# 1_P1.net
KiCad netlist of a schematic drawn in Altium Designer
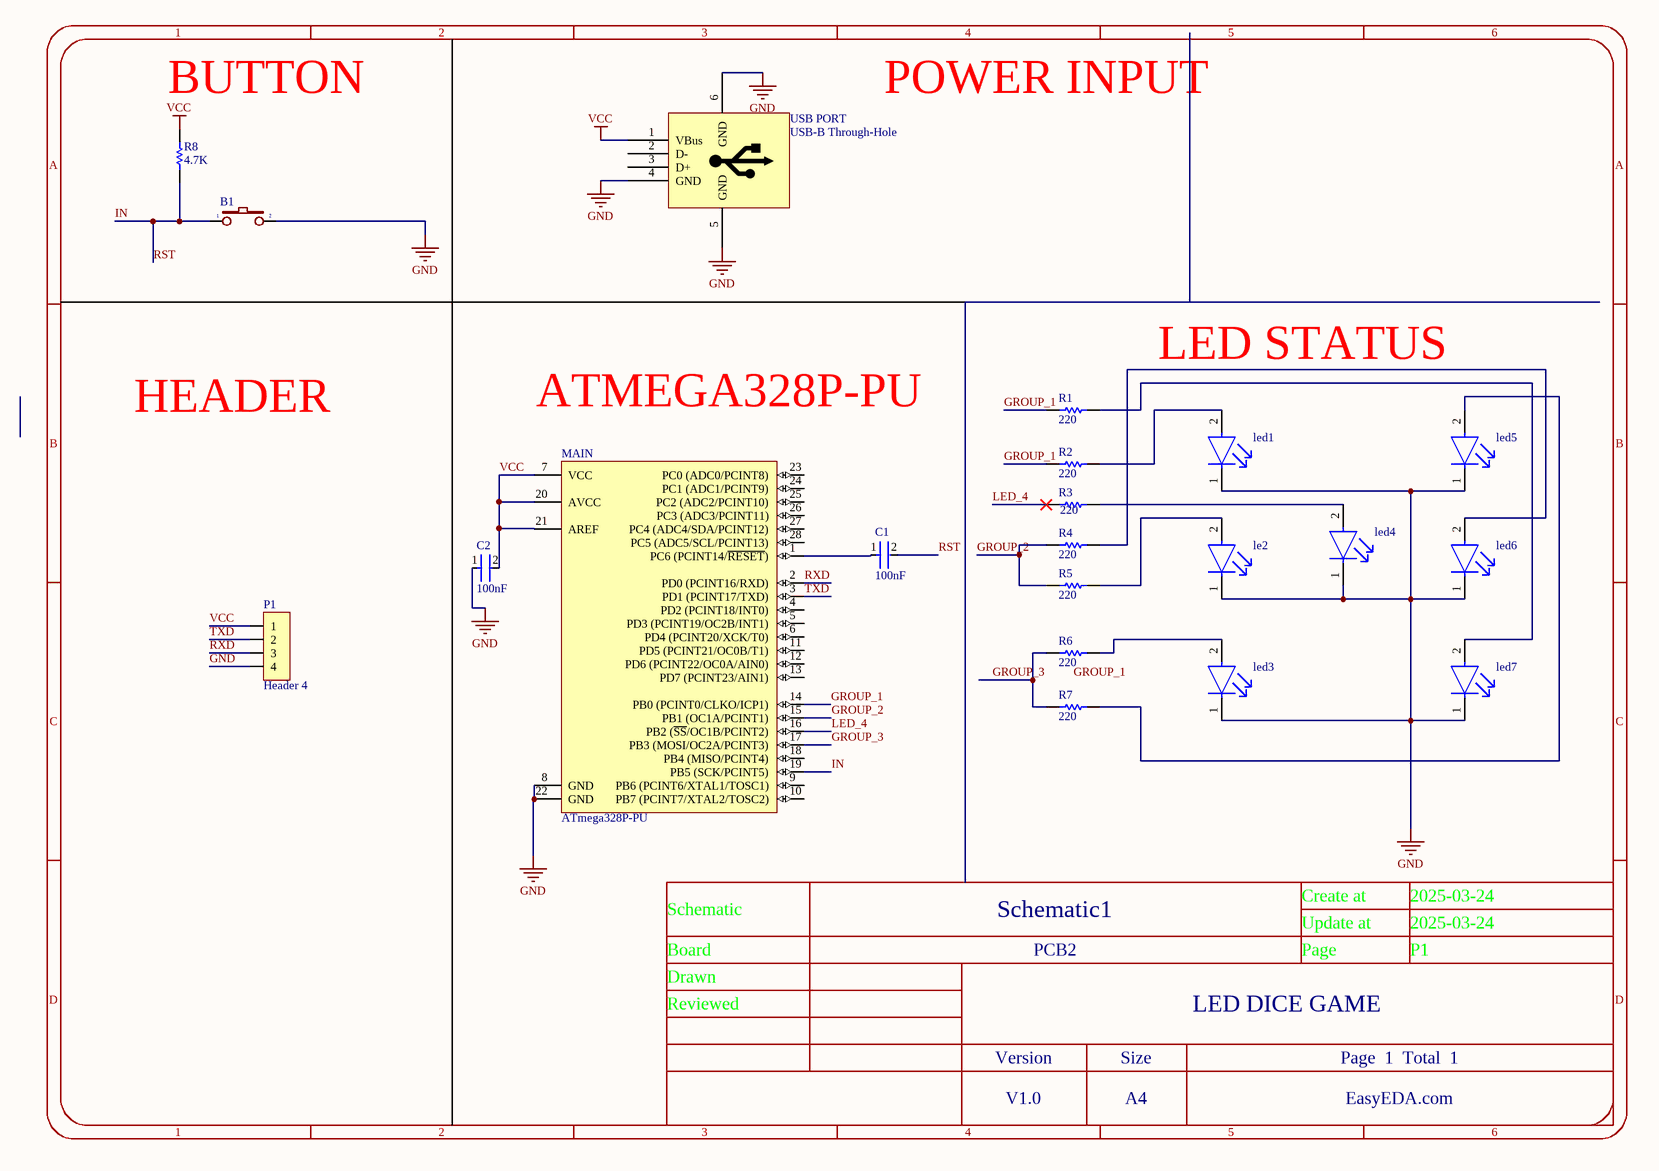
[diagram p0: 1_P1.schdoc]

(export (version "E")
  (design (tool "Eeschema 10.0.6"))
  (components
    (comp (ref "B1")
      (value "~")
      (footprint "SW2")
      (description "Switch button 2 pin")
      (libsource (lib "Cty1") (part "SW2"))
    )
    (comp (ref "C1")
      (value "100nF")
      (footprint "FP-C0402-BB-MFG")
      (description "CAP CER 0.1UF 10V X5R 0402")
      (fields (field (name "MANUFACTURER") "Kemet") (field (name "TOLERANCE") "0.1"))
      (libsource (lib "Altium Content Vault") (part "b4654b650e69147ec39a6b967a45e02"))
    )
    (comp (ref "C2")
      (value "100nF")
      (footprint "FP-C0402-BB-MFG")
      (description "CAP CER 0.1UF 10V X5R 0402")
      (fields (field (name "MANUFACTURER") "Kemet") (field (name "TOLERANCE") "0.1"))
      (libsource (lib "Altium Content Vault") (part "b4654b650e69147ec39a6b967a45e02"))
    )
    (comp (ref "le2")
      (value "~")
      (footprint "FP-HLMP-1719-MFG")
      (description "LED YELLOW DIFFUSED T-1 T/H")
      (fields
        (field (name "MANUFACTURER") "Broadcom")
        (field (name "OCTOPART") "https://octopart.com/hlmp-1719-broadcom-71130405")
      )
      (libsource (lib "Altium Content Vault") (part "8706943c75ba83719d021d2fdc84c58"))
    )
    (comp (ref "led1")
      (value "~")
      (footprint "FP-HLMP-1719-MFG")
      (description "LED YELLOW DIFFUSED T-1 T/H")
      (fields
        (field (name "MANUFACTURER") "Broadcom")
        (field (name "OCTOPART") "https://octopart.com/hlmp-1719-broadcom-71130405")
      )
      (libsource (lib "Altium Content Vault") (part "8706943c75ba83719d021d2fdc84c58"))
    )
    (comp (ref "led3")
      (value "~")
      (footprint "FP-HLMP-1719-MFG")
      (description "LED YELLOW DIFFUSED T-1 T/H")
      (fields
        (field (name "MANUFACTURER") "Broadcom")
        (field (name "OCTOPART") "https://octopart.com/hlmp-1719-broadcom-71130405")
      )
      (libsource (lib "Altium Content Vault") (part "8706943c75ba83719d021d2fdc84c58"))
    )
    (comp (ref "led4")
      (value "~")
      (footprint "FP-HLMP-1719-MFG")
      (description "LED YELLOW DIFFUSED T-1 T/H")
      (fields
        (field (name "MANUFACTURER") "Broadcom")
        (field (name "OCTOPART") "https://octopart.com/hlmp-1719-broadcom-71130405")
      )
      (libsource (lib "Altium Content Vault") (part "8706943c75ba83719d021d2fdc84c58"))
    )
    (comp (ref "led5")
      (value "~")
      (footprint "FP-HLMP-1719-MFG")
      (description "LED YELLOW DIFFUSED T-1 T/H")
      (fields
        (field (name "MANUFACTURER") "Broadcom")
        (field (name "OCTOPART") "https://octopart.com/hlmp-1719-broadcom-71130405")
      )
      (libsource (lib "Altium Content Vault") (part "8706943c75ba83719d021d2fdc84c58"))
    )
    (comp (ref "led6")
      (value "~")
      (footprint "FP-HLMP-1719-MFG")
      (description "LED YELLOW DIFFUSED T-1 T/H")
      (fields
        (field (name "MANUFACTURER") "Broadcom")
        (field (name "OCTOPART") "https://octopart.com/hlmp-1719-broadcom-71130405")
      )
      (libsource (lib "Altium Content Vault") (part "8706943c75ba83719d021d2fdc84c58"))
    )
    (comp (ref "led7")
      (value "~")
      (footprint "FP-HLMP-1719-MFG")
      (description "LED YELLOW DIFFUSED T-1 T/H")
      (fields
        (field (name "MANUFACTURER") "Broadcom")
        (field (name "OCTOPART") "https://octopart.com/hlmp-1719-broadcom-71130405")
      )
      (libsource (lib "Altium Content Vault") (part "8706943c75ba83719d021d2fdc84c58"))
    )
    (comp (ref "MAIN")
      (value "ATmega328P-PU")
      (footprint "28P3")
      (libsource (lib "Altium Content Vault") (part "MC-8B-ATM48-IL28"))
    )
    (comp (ref "P1")
      (value "Header 4")
      (footprint "HDR/Header/4/2mm")
      (description "Header, 4-Pin")
      (libsource (lib "connectors") (part "Header 4"))
    )
    (comp (ref "R1")
      (value "220")
      (footprint "RESC1609X50X30NL8T20")
      (description "Chip Resistor, 10 KOhm, +/- 1%, 100 mW, -55 to 155 degC, 0603 (1608 Metric), RoHS, Tape and Reel")
      (fields (field (name "MANUFACTURER") "Vishay Semiconductor"))
      (libsource (lib "Altium Content Vault") (part "RES-2"))
    )
    (comp (ref "R2")
      (value "220")
      (footprint "RESC1609X50X30NL8T20")
      (description "Chip Resistor, 10 KOhm, +/- 1%, 100 mW, -55 to 155 degC, 0603 (1608 Metric), RoHS, Tape and Reel")
      (fields (field (name "MANUFACTURER") "Vishay Semiconductor"))
      (libsource (lib "Altium Content Vault") (part "RES-2"))
    )
    (comp (ref "R3")
      (value "220")
      (footprint "RESC1609X50X30NL8T20")
      (description "Chip Resistor, 10 KOhm, +/- 1%, 100 mW, -55 to 155 degC, 0603 (1608 Metric), RoHS, Tape and Reel")
      (fields (field (name "MANUFACTURER") "Vishay Semiconductor"))
      (libsource (lib "Altium Content Vault") (part "RES-2"))
    )
    (comp (ref "R4")
      (value "220")
      (footprint "RESC1609X50X30NL8T20")
      (description "Chip Resistor, 10 KOhm, +/- 1%, 100 mW, -55 to 155 degC, 0603 (1608 Metric), RoHS, Tape and Reel")
      (fields (field (name "MANUFACTURER") "Vishay Semiconductor"))
      (libsource (lib "Altium Content Vault") (part "RES-2"))
    )
    (comp (ref "R5")
      (value "220")
      (footprint "RESC1609X50X30NL8T20")
      (description "Chip Resistor, 10 KOhm, +/- 1%, 100 mW, -55 to 155 degC, 0603 (1608 Metric), RoHS, Tape and Reel")
      (fields (field (name "MANUFACTURER") "Vishay Semiconductor"))
      (libsource (lib "Altium Content Vault") (part "RES-2"))
    )
    (comp (ref "R6")
      (value "220")
      (footprint "RESC1609X50X30NL8T20")
      (description "Chip Resistor, 10 KOhm, +/- 1%, 100 mW, -55 to 155 degC, 0603 (1608 Metric), RoHS, Tape and Reel")
      (fields (field (name "MANUFACTURER") "Vishay Semiconductor"))
      (libsource (lib "Altium Content Vault") (part "RES-2"))
    )
    (comp (ref "R7")
      (value "220")
      (footprint "RESC1609X50X30NL8T20")
      (description "Chip Resistor, 10 KOhm, +/- 1%, 100 mW, -55 to 155 degC, 0603 (1608 Metric), RoHS, Tape and Reel")
      (fields (field (name "MANUFACTURER") "Vishay Semiconductor"))
      (libsource (lib "Altium Content Vault") (part "RES-2"))
    )
    (comp (ref "R8")
      (value "4.7K")
      (footprint "RESC1609X50X30NL8T20")
      (description "Chip Resistor, 10 KOhm, +/- 1%, 100 mW, -55 to 155 degC, 0603 (1608 Metric), RoHS, Tape and Reel")
      (fields (field (name "MANUFACTURER") "Vishay Semiconductor"))
      (libsource (lib "Altium Content Vault") (part "RES-2"))
    )
    (comp (ref "USB PORT")
      (value "USB-B Through-Hole")
      (footprint "USB2.5-2H4D")
      (libsource (lib "Cty1") (part "USB-B TH"))
    )
  )
  (nets
    (net (code "1") (name "/GROUP_1") (class "Default")
      (node (ref "MAIN") (pin "14") (pinfunction "PB0_(PCINT0/CLKO/ICP1)_14") (pintype "bidirectional"))
      (node (ref "R1") (pin "1") (pinfunction "1_1") (pintype "passive"))
      (node (ref "R2") (pin "1") (pinfunction "1_1") (pintype "passive"))
    )
    (net (code "2") (name "/GROUP_2") (class "Default")
      (node (ref "MAIN") (pin "15") (pinfunction "PB1_(OC1A/PCINT1)_15") (pintype "bidirectional"))
      (node (ref "R4") (pin "1") (pinfunction "1_1") (pintype "passive"))
      (node (ref "R5") (pin "1") (pinfunction "1_1") (pintype "passive"))
    )
    (net (code "3") (name "/GROUP_3") (class "Default")
      (node (ref "MAIN") (pin "17") (pinfunction "PB3_(MOSI/OC2A/PCINT3)_17") (pintype "bidirectional"))
      (node (ref "R6") (pin "1") (pinfunction "1_1") (pintype "passive"))
      (node (ref "R7") (pin "1") (pinfunction "1_1") (pintype "passive"))
    )
    (net (code "4") (name "/IN") (class "Default")
      (node (ref "B1") (pin "1") (pinfunction "1_1") (pintype "passive"))
      (node (ref "C1") (pin "2") (pinfunction "2_2") (pintype "passive"))
      (node (ref "MAIN") (pin "19") (pinfunction "PB5_(SCK/PCINT5)_19") (pintype "bidirectional"))
      (node (ref "R8") (pin "1") (pinfunction "1_1") (pintype "passive"))
    )
    (net (code "5") (name "/LED_4") (class "Default")
      (node (ref "MAIN") (pin "16") (pinfunction "PB2_(~{SS}/OC1B/PCINT2)_16") (pintype "bidirectional"))
      (node (ref "R3") (pin "1") (pinfunction "1_1") (pintype "passive"))
    )
    (net (code "6") (name "/RXD") (class "Default")
      (node (ref "MAIN") (pin "2") (pinfunction "PD0_(PCINT16/RXD)_2") (pintype "bidirectional"))
      (node (ref "P1") (pin "3") (pinfunction "3_3") (pintype "passive"))
    )
    (net (code "7") (name "/TXD") (class "Default")
      (node (ref "MAIN") (pin "3") (pinfunction "PD1_(PCINT17/TXD)_3") (pintype "bidirectional"))
      (node (ref "P1") (pin "2") (pinfunction "2_2") (pintype "passive"))
    )
    (net (code "8") (name "GND") (class "Default")
      (node (ref "B1") (pin "2") (pinfunction "2_2") (pintype "passive"))
      (node (ref "C2") (pin "1") (pinfunction "1_1") (pintype "passive"))
      (node (ref "MAIN") (pin "22") (pinfunction "GND_22") (pintype "power_in"))
      (node (ref "MAIN") (pin "8") (pinfunction "GND_8") (pintype "power_in"))
      (node (ref "P1") (pin "4") (pinfunction "4_4") (pintype "passive"))
      (node (ref "USB PORT") (pin "4") (pinfunction "GND_4") (pintype "passive"))
      (node (ref "USB PORT") (pin "5") (pinfunction "GND_5") (pintype "passive"))
      (node (ref "USB PORT") (pin "6") (pinfunction "GND_6") (pintype "passive"))
      (node (ref "le2") (pin "1") (pinfunction "C_1") (pintype "passive"))
      (node (ref "led1") (pin "1") (pinfunction "C_1") (pintype "passive"))
      (node (ref "led3") (pin "1") (pinfunction "C_1") (pintype "passive"))
      (node (ref "led4") (pin "1") (pinfunction "C_1") (pintype "passive"))
      (node (ref "led5") (pin "1") (pinfunction "C_1") (pintype "passive"))
      (node (ref "led6") (pin "1") (pinfunction "C_1") (pintype "passive"))
      (node (ref "led7") (pin "1") (pinfunction "C_1") (pintype "passive"))
    )
    (net (code "9") (name "Net-(MAIN-PC6_(PCINT14{slash}~{RESET}))") (class "Default")
      (node (ref "C1") (pin "1") (pinfunction "1_1") (pintype "passive"))
      (node (ref "MAIN") (pin "1") (pinfunction "PC6_(PCINT14/~{RESET})_1") (pintype "bidirectional"))
    )
    (net (code "10") (name "Net-(le2-A)") (class "Default")
      (node (ref "R5") (pin "2") (pinfunction "2_2") (pintype "passive"))
      (node (ref "le2") (pin "2") (pinfunction "A_2") (pintype "passive"))
    )
    (net (code "11") (name "Net-(led1-A)") (class "Default")
      (node (ref "R2") (pin "2") (pinfunction "2_2") (pintype "passive"))
      (node (ref "led1") (pin "2") (pinfunction "A_2") (pintype "passive"))
    )
    (net (code "12") (name "Net-(led3-A)") (class "Default")
      (node (ref "R6") (pin "2") (pinfunction "2_2") (pintype "passive"))
      (node (ref "led3") (pin "2") (pinfunction "A_2") (pintype "passive"))
    )
    (net (code "13") (name "Net-(led4-A)") (class "Default")
      (node (ref "R3") (pin "2") (pinfunction "2_2") (pintype "passive"))
      (node (ref "led4") (pin "2") (pinfunction "A_2") (pintype "passive"))
    )
    (net (code "14") (name "Net-(led5-A)") (class "Default")
      (node (ref "R7") (pin "2") (pinfunction "2_2") (pintype "passive"))
      (node (ref "led5") (pin "2") (pinfunction "A_2") (pintype "passive"))
    )
    (net (code "15") (name "Net-(led6-A)") (class "Default")
      (node (ref "R4") (pin "2") (pinfunction "2_2") (pintype "passive"))
      (node (ref "led6") (pin "2") (pinfunction "A_2") (pintype "passive"))
    )
    (net (code "16") (name "Net-(led7-A)") (class "Default")
      (node (ref "R1") (pin "2") (pinfunction "2_2") (pintype "passive"))
      (node (ref "led7") (pin "2") (pinfunction "A_2") (pintype "passive"))
    )
    (net (code "17") (name "VCC") (class "Default")
      (node (ref "C2") (pin "2") (pinfunction "2_2") (pintype "passive"))
      (node (ref "MAIN") (pin "20") (pinfunction "AVCC_20") (pintype "power_in"))
      (node (ref "MAIN") (pin "21") (pinfunction "AREF_21") (pintype "power_in"))
      (node (ref "MAIN") (pin "7") (pinfunction "VCC_7") (pintype "power_in"))
      (node (ref "P1") (pin "1") (pinfunction "1_1") (pintype "passive"))
      (node (ref "R8") (pin "2") (pinfunction "2_2") (pintype "passive"))
      (node (ref "USB PORT") (pin "1") (pinfunction "VBus_1") (pintype "passive"))
    )
    (net (code "18") (name "unconnected-(MAIN-PB4_(MISO{slash}PCINT4)-Pad18)") (class "Default")
      (node (ref "MAIN") (pin "18") (pinfunction "PB4_(MISO/PCINT4)_18") (pintype "bidirectional"))
    )
    (net (code "19") (name "unconnected-(MAIN-PB6_(PCINT6{slash}XTAL1{slash}TOSC1)-Pad9)") (class "Default")
      (node (ref "MAIN") (pin "9") (pinfunction "PB6_(PCINT6/XTAL1/TOSC1)_9") (pintype "bidirectional"))
    )
    (net (code "20") (name "unconnected-(MAIN-PB7_(PCINT7{slash}XTAL2{slash}TOSC2)-Pad10)") (class "Default")
      (node (ref "MAIN") (pin "10") (pinfunction "PB7_(PCINT7/XTAL2/TOSC2)_10") (pintype "bidirectional"))
    )
    (net (code "21") (name "unconnected-(MAIN-PC0_(ADC0{slash}PCINT8)-Pad23)") (class "Default")
      (node (ref "MAIN") (pin "23") (pinfunction "PC0_(ADC0/PCINT8)_23") (pintype "bidirectional"))
    )
    (net (code "22") (name "unconnected-(MAIN-PC1_(ADC1{slash}PCINT9)-Pad24)") (class "Default")
      (node (ref "MAIN") (pin "24") (pinfunction "PC1_(ADC1/PCINT9)_24") (pintype "bidirectional"))
    )
    (net (code "23") (name "unconnected-(MAIN-PC2_(ADC2{slash}PCINT10)-Pad25)") (class "Default")
      (node (ref "MAIN") (pin "25") (pinfunction "PC2_(ADC2/PCINT10)_25") (pintype "bidirectional"))
    )
    (net (code "24") (name "unconnected-(MAIN-PC3_(ADC3{slash}PCINT11)-Pad26)") (class "Default")
      (node (ref "MAIN") (pin "26") (pinfunction "PC3_(ADC3/PCINT11)_26") (pintype "bidirectional"))
    )
    (net (code "25") (name "unconnected-(MAIN-PC4_(ADC4{slash}SDA{slash}PCINT12)-Pad27)") (class "Default")
      (node (ref "MAIN") (pin "27") (pinfunction "PC4_(ADC4/SDA/PCINT12)_27") (pintype "bidirectional"))
    )
    (net (code "26") (name "unconnected-(MAIN-PC5_(ADC5{slash}SCL{slash}PCINT13)-Pad28)") (class "Default")
      (node (ref "MAIN") (pin "28") (pinfunction "PC5_(ADC5/SCL/PCINT13)_28") (pintype "bidirectional"))
    )
    (net (code "27") (name "unconnected-(MAIN-PD2_(PCINT18{slash}INT0)-Pad4)") (class "Default")
      (node (ref "MAIN") (pin "4") (pinfunction "PD2_(PCINT18/INT0)_4") (pintype "bidirectional"))
    )
    (net (code "28") (name "unconnected-(MAIN-PD3_(PCINT19{slash}OC2B{slash}INT1)-Pad5)") (class "Default")
      (node (ref "MAIN") (pin "5") (pinfunction "PD3_(PCINT19/OC2B/INT1)_5") (pintype "bidirectional"))
    )
    (net (code "29") (name "unconnected-(MAIN-PD4_(PCINT20{slash}XCK{slash}T0)-Pad6)") (class "Default")
      (node (ref "MAIN") (pin "6") (pinfunction "PD4_(PCINT20/XCK/T0)_6") (pintype "bidirectional"))
    )
    (net (code "30") (name "unconnected-(MAIN-PD5_(PCINT21{slash}OC0B{slash}T1)-Pad11)") (class "Default")
      (node (ref "MAIN") (pin "11") (pinfunction "PD5_(PCINT21/OC0B/T1)_11") (pintype "bidirectional"))
    )
    (net (code "31") (name "unconnected-(MAIN-PD6_(PCINT22{slash}OC0A{slash}AIN0)-Pad12)") (class "Default")
      (node (ref "MAIN") (pin "12") (pinfunction "PD6_(PCINT22/OC0A/AIN0)_12") (pintype "bidirectional"))
    )
    (net (code "32") (name "unconnected-(MAIN-PD7_(PCINT23{slash}AIN1)-Pad13)") (class "Default")
      (node (ref "MAIN") (pin "13") (pinfunction "PD7_(PCINT23/AIN1)_13") (pintype "bidirectional"))
    )
    (net (code "33") (name "unconnected-(USB PORT-D+-Pad3)") (class "Default")
      (node (ref "USB PORT") (pin "3") (pinfunction "D+_3") (pintype "passive"))
    )
    (net (code "34") (name "unconnected-(USB PORT-D--Pad2)") (class "Default")
      (node (ref "USB PORT") (pin "2") (pinfunction "D-_2") (pintype "passive"))
    )
  )
)
